# QBar-Graph-V1.net
KiCad netlist of a schematic drawn in EAGLE
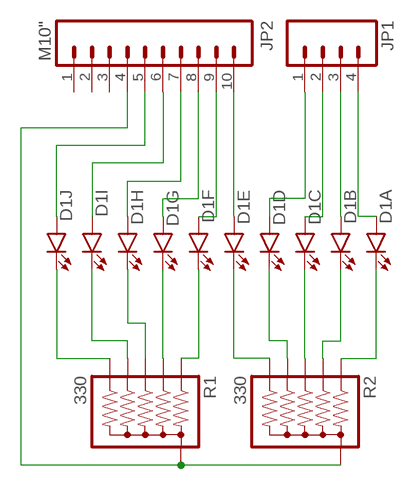
[diagram p0: schematic, sheet 1]

(export (version "E")
  (design (tool "Eeschema 10.0.6"))
  (components
    (comp (ref "D1")
      (value "LED_BARGRAPH_10")
      (footprint "eagle-import:LED_BARGAPH_10")
      (libsource (lib "eagle-import") (part "LED_BARGRAPH_10"))
    )
    (comp (ref "JP1")
      (value "M04PTH")
      (footprint "eagle-import:1X04")
      (libsource (lib "eagle-import") (part "M04PTH"))
    )
    (comp (ref "JP2")
      (value "M10\"")
      (footprint "eagle-import:1X10")
      (libsource (lib "eagle-import") (part "M10{dblquote}"))
    )
    (comp (ref "R1")
      (value "330")
      (footprint "eagle-import:RPACK-SIP-PTH-5")
      (libsource (lib "eagle-import") (part "RPACK-BUSSED-SIP-PTH-5"))
    )
    (comp (ref "R2")
      (value "330")
      (footprint "eagle-import:RPACK-SIP-PTH-5")
      (libsource (lib "eagle-import") (part "RPACK-BUSSED-SIP-PTH-5"))
    )
  )
  (nets
    (net (code "1") (name "Net-(D1A-A)") (class "Default")
      (node (ref "D1") (pin "1") (pinfunction "A_1") (pintype "passive"))
      (node (ref "JP1") (pin "4") (pinfunction "4_4") (pintype "passive"))
    )
    (net (code "2") (name "Net-(D1A-C)") (class "Default")
      (node (ref "D1") (pin "20") (pinfunction "C_20") (pintype "passive"))
      (node (ref "R2") (pin "P$2") (pinfunction "2_P$2") (pintype "passive"))
    )
    (net (code "3") (name "Net-(D1B-A)") (class "Default")
      (node (ref "D1") (pin "2") (pinfunction "A_2") (pintype "passive"))
      (node (ref "JP1") (pin "3") (pinfunction "3_3") (pintype "passive"))
    )
    (net (code "4") (name "Net-(D1B-C)") (class "Default")
      (node (ref "D1") (pin "19") (pinfunction "C_19") (pintype "passive"))
      (node (ref "R2") (pin "P$3") (pinfunction "3_P$3") (pintype "passive"))
    )
    (net (code "5") (name "Net-(D1C-A)") (class "Default")
      (node (ref "D1") (pin "3") (pinfunction "A_3") (pintype "passive"))
      (node (ref "JP1") (pin "2") (pinfunction "2_2") (pintype "passive"))
    )
    (net (code "6") (name "Net-(D1C-C)") (class "Default")
      (node (ref "D1") (pin "18") (pinfunction "C_18") (pintype "passive"))
      (node (ref "R2") (pin "P$4") (pinfunction "4_P$4") (pintype "passive"))
    )
    (net (code "7") (name "Net-(D1D-A)") (class "Default")
      (node (ref "D1") (pin "4") (pinfunction "A_4") (pintype "passive"))
      (node (ref "JP1") (pin "1") (pinfunction "1_1") (pintype "passive"))
    )
    (net (code "8") (name "Net-(D1D-C)") (class "Default")
      (node (ref "D1") (pin "17") (pinfunction "C_17") (pintype "passive"))
      (node (ref "R2") (pin "P$5") (pinfunction "5_P$5") (pintype "passive"))
    )
    (net (code "9") (name "Net-(D1E-A)") (class "Default")
      (node (ref "D1") (pin "5") (pinfunction "A_5") (pintype "passive"))
      (node (ref "JP2") (pin "10") (pinfunction "10_10") (pintype "passive"))
    )
    (net (code "10") (name "Net-(D1E-C)") (class "Default")
      (node (ref "D1") (pin "16") (pinfunction "C_16") (pintype "passive"))
      (node (ref "R2") (pin "P$6") (pinfunction "6_P$6") (pintype "passive"))
    )
    (net (code "11") (name "Net-(D1F-A)") (class "Default")
      (node (ref "D1") (pin "6") (pinfunction "A_6") (pintype "passive"))
      (node (ref "JP2") (pin "9") (pinfunction "9_9") (pintype "passive"))
    )
    (net (code "12") (name "Net-(D1F-C)") (class "Default")
      (node (ref "D1") (pin "15") (pinfunction "C_15") (pintype "passive"))
      (node (ref "R1") (pin "P$2") (pinfunction "2_P$2") (pintype "passive"))
    )
    (net (code "13") (name "Net-(D1G-A)") (class "Default")
      (node (ref "D1") (pin "7") (pinfunction "A_7") (pintype "passive"))
      (node (ref "JP2") (pin "8") (pinfunction "8_8") (pintype "passive"))
    )
    (net (code "14") (name "Net-(D1G-C)") (class "Default")
      (node (ref "D1") (pin "14") (pinfunction "C_14") (pintype "passive"))
      (node (ref "R1") (pin "P$3") (pinfunction "3_P$3") (pintype "passive"))
    )
    (net (code "15") (name "Net-(D1H-A)") (class "Default")
      (node (ref "D1") (pin "8") (pinfunction "A_8") (pintype "passive"))
      (node (ref "JP2") (pin "7") (pinfunction "7_7") (pintype "passive"))
    )
    (net (code "16") (name "Net-(D1H-C)") (class "Default")
      (node (ref "D1") (pin "13") (pinfunction "C_13") (pintype "passive"))
      (node (ref "R1") (pin "P$4") (pinfunction "4_P$4") (pintype "passive"))
    )
    (net (code "17") (name "Net-(D1I-A)") (class "Default")
      (node (ref "D1") (pin "9") (pinfunction "A_9") (pintype "passive"))
      (node (ref "JP2") (pin "6") (pinfunction "6_6") (pintype "passive"))
    )
    (net (code "18") (name "Net-(D1I-C)") (class "Default")
      (node (ref "D1") (pin "12") (pinfunction "C_12") (pintype "passive"))
      (node (ref "R1") (pin "P$5") (pinfunction "5_P$5") (pintype "passive"))
    )
    (net (code "19") (name "Net-(D1J-A)") (class "Default")
      (node (ref "D1") (pin "10") (pinfunction "A_10") (pintype "passive"))
      (node (ref "JP2") (pin "5") (pinfunction "5_5") (pintype "passive"))
    )
    (net (code "20") (name "Net-(D1J-C)") (class "Default")
      (node (ref "D1") (pin "11") (pinfunction "C_11") (pintype "passive"))
      (node (ref "R1") (pin "P$6") (pinfunction "6_P$6") (pintype "passive"))
    )
    (net (code "21") (name "Net-(R1-1)") (class "Default")
      (node (ref "JP2") (pin "4") (pinfunction "4_4") (pintype "passive"))
      (node (ref "R1") (pin "P$1") (pinfunction "1_P$1") (pintype "passive"))
      (node (ref "R2") (pin "P$1") (pinfunction "1_P$1") (pintype "passive"))
    )
    (net (code "22") (name "unconnected-(JP2-Pad1)") (class "Default")
      (node (ref "JP2") (pin "1") (pinfunction "1_1") (pintype "passive"))
    )
    (net (code "23") (name "unconnected-(JP2-Pad2)") (class "Default")
      (node (ref "JP2") (pin "2") (pinfunction "2_2") (pintype "passive"))
    )
    (net (code "24") (name "unconnected-(JP2-Pad3)") (class "Default")
      (node (ref "JP2") (pin "3") (pinfunction "3_3") (pintype "passive"))
    )
  )
)
